# Other_Components.net
KiCad netlist of a schematic drawn in Altium Designer
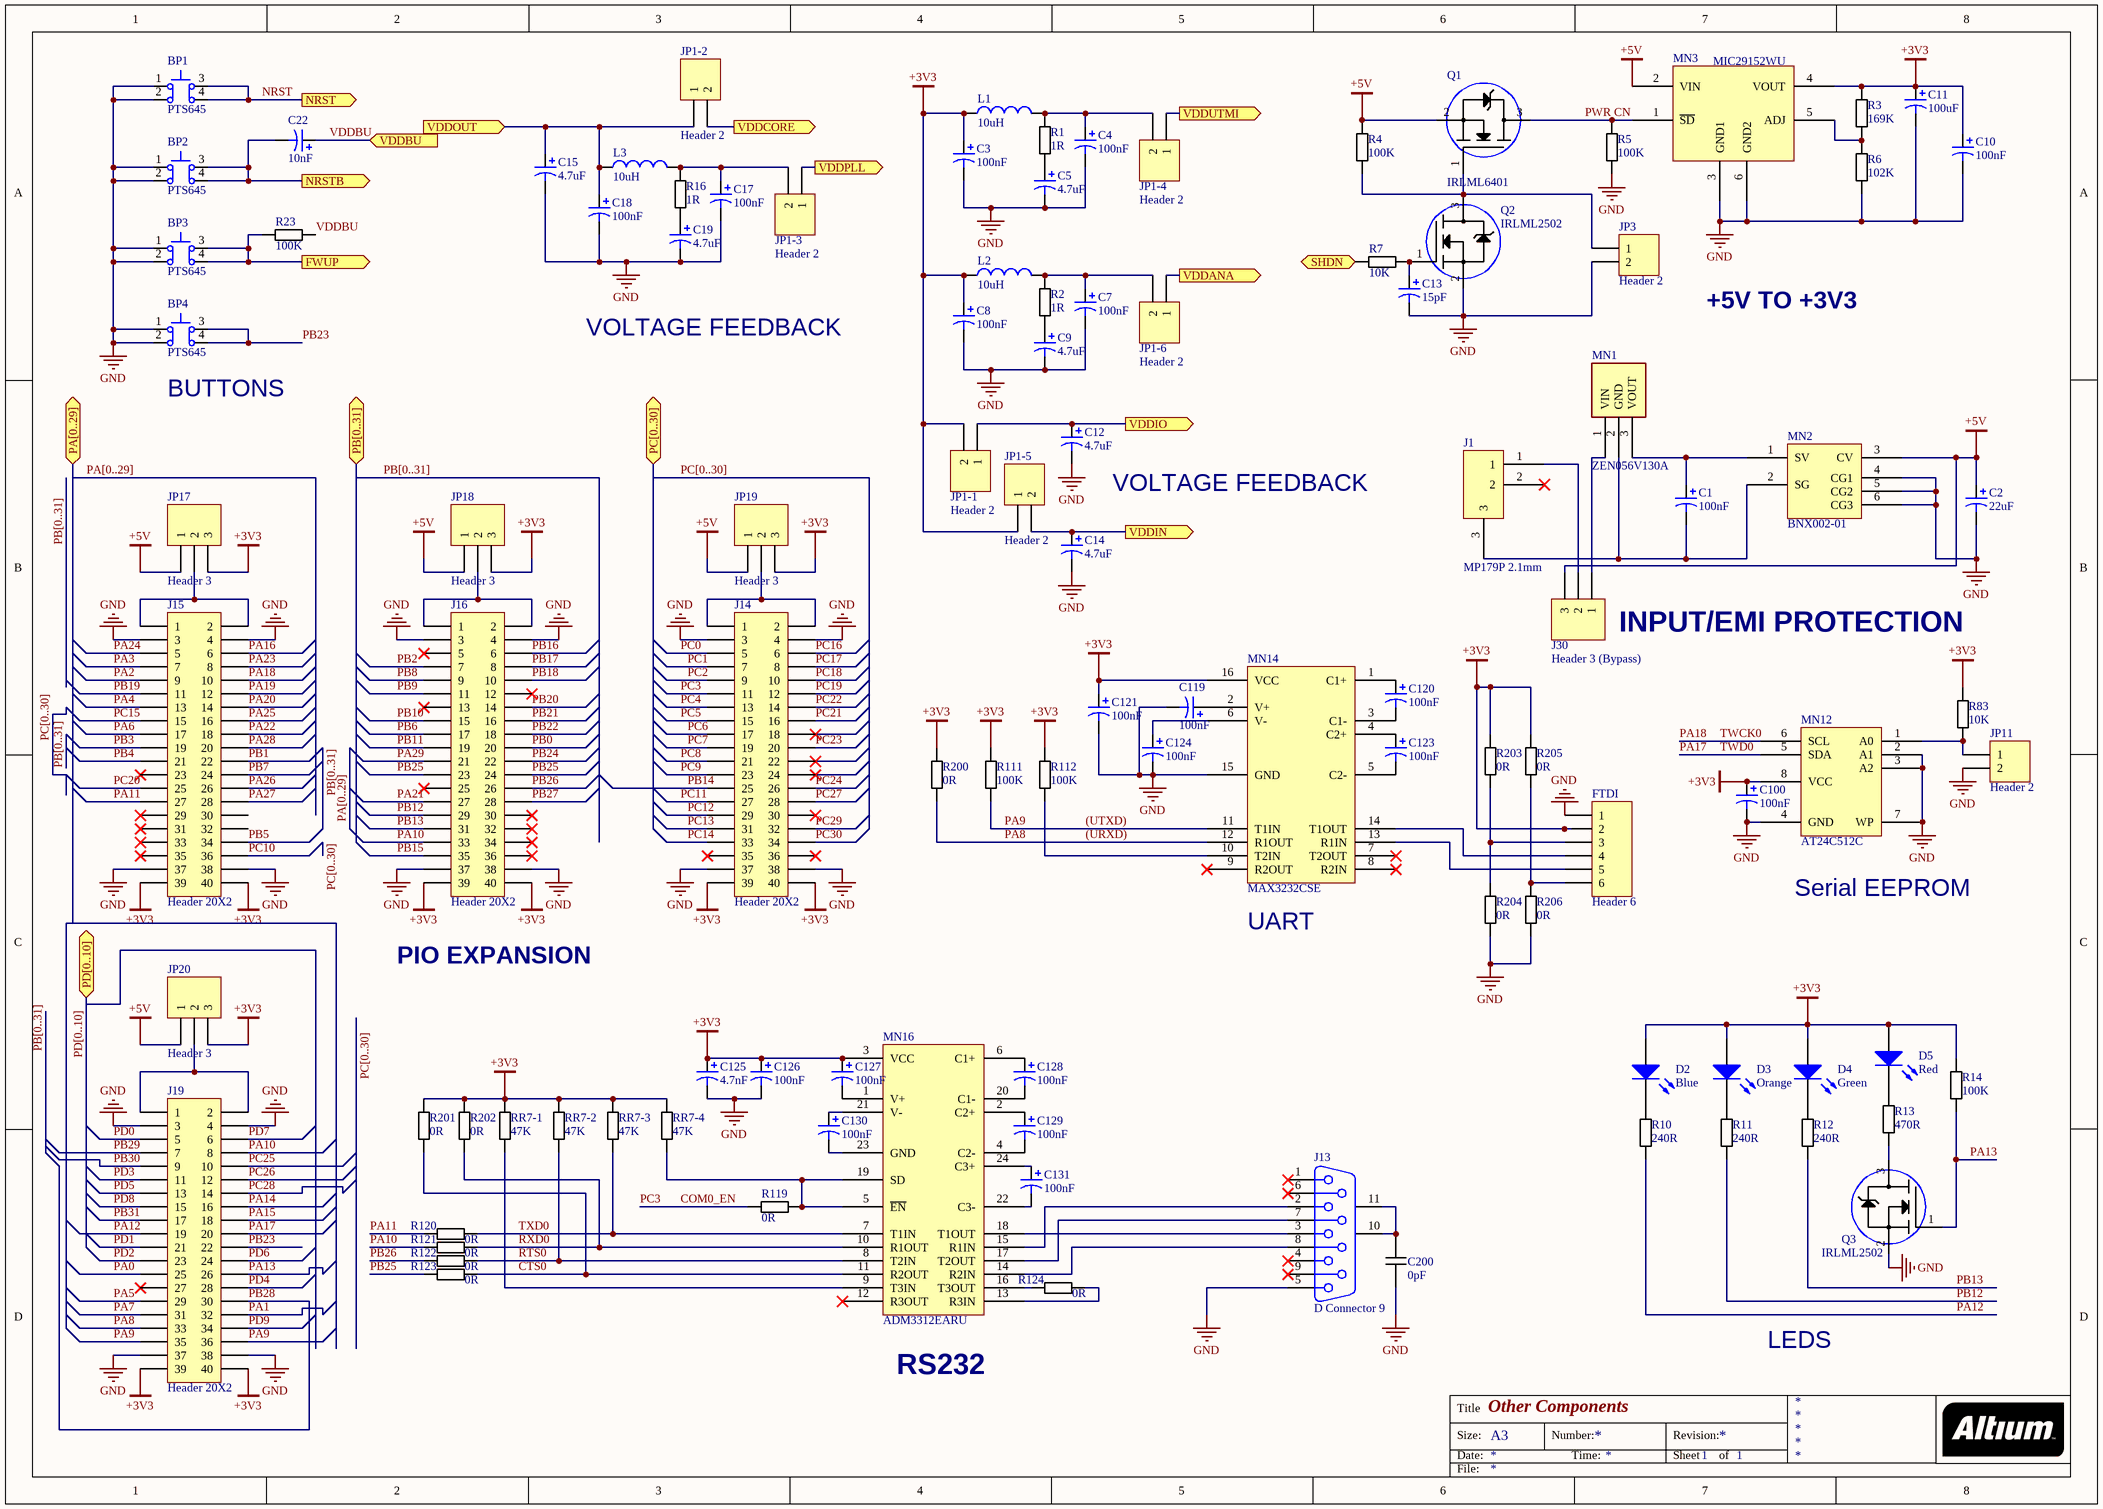
[diagram p0: Other Components.SchDoc]

(export (version "E")
  (design (tool "Eeschema 10.0.6"))
  (components
    (comp (ref "BP1")
      (value "PTS645")
      (footprint "PTS645")
      (description "Digi-Key Part Number CKN9112CT-ND")
      (fields (field (name "PUBLISHER") "Altium Limited"))
      (libsource (lib "IL Switch Push Button") (part "PTS645"))
    )
    (comp (ref "BP2")
      (value "PTS645")
      (footprint "PTS645")
      (description "Digi-Key Part Number CKN9112CT-ND")
      (fields (field (name "PUBLISHER") "Altium Limited"))
      (libsource (lib "IL Switch Push Button") (part "PTS645"))
    )
    (comp (ref "BP3")
      (value "PTS645")
      (footprint "PTS645")
      (description "Digi-Key Part Number CKN9112CT-ND")
      (fields (field (name "PUBLISHER") "Altium Limited"))
      (libsource (lib "IL Switch Push Button") (part "PTS645"))
    )
    (comp (ref "BP4")
      (value "PTS645")
      (footprint "PTS645")
      (description "Digi-Key Part Number CKN9112CT-ND")
      (fields (field (name "PUBLISHER") "Altium Limited"))
      (libsource (lib "IL Switch Push Button") (part "PTS645"))
    )
    (comp (ref "C1")
      (value "100nF")
      (footprint "0805 Cap")
      (description "Polarized Capacitor (Surface Mount)")
      (fields (field (name "Comment") "Cap Pol3") (field (name "PUBLISHER") "Altium Limited"))
      (libsource (lib "Miscellaneous Devices") (part "Cap Pol3"))
    )
    (comp (ref "C2")
      (value "22uF")
      (footprint "0805 Cap")
      (description "Not sure if this one should be 0805?")
      (fields (field (name "Comment") "Cap Pol3") (field (name "PUBLISHER") "Altium Limited"))
      (libsource (lib "Miscellaneous Devices") (part "Cap Pol3"))
    )
    (comp (ref "C3")
      (value "100nF")
      (footprint "0805 Cap")
      (description "Polarized Capacitor (Surface Mount)")
      (fields (field (name "Comment") "Cap Pol3") (field (name "PUBLISHER") "Altium Limited"))
      (libsource (lib "Miscellaneous Devices") (part "Cap Pol3"))
    )
    (comp (ref "C4")
      (value "100nF")
      (footprint "0805 Cap")
      (description "Polarized Capacitor (Surface Mount)")
      (fields (field (name "Comment") "Cap Pol3") (field (name "PUBLISHER") "Altium Limited"))
      (libsource (lib "Miscellaneous Devices") (part "Cap Pol3"))
    )
    (comp (ref "C5")
      (value "4.7uF")
      (footprint "0805 Cap")
      (description "Polarized Capacitor (Surface Mount)")
      (fields (field (name "Comment") "Cap Pol3") (field (name "PUBLISHER") "Altium Limited"))
      (libsource (lib "Miscellaneous Devices") (part "Cap Pol3"))
    )
    (comp (ref "C7")
      (value "100nF")
      (footprint "0805 Cap")
      (description "Polarized Capacitor (Surface Mount)")
      (fields (field (name "Comment") "Cap Pol3") (field (name "PUBLISHER") "Altium Limited"))
      (libsource (lib "Miscellaneous Devices") (part "Cap Pol3"))
    )
    (comp (ref "C8")
      (value "100nF")
      (footprint "0805 Cap")
      (description "Polarized Capacitor (Surface Mount)")
      (fields (field (name "Comment") "Cap Pol3") (field (name "PUBLISHER") "Altium Limited"))
      (libsource (lib "Miscellaneous Devices") (part "Cap Pol3"))
    )
    (comp (ref "C9")
      (value "4.7uF")
      (footprint "0805 Cap")
      (description "Polarized Capacitor (Surface Mount)")
      (fields (field (name "Comment") "Cap Pol3") (field (name "PUBLISHER") "Altium Limited"))
      (libsource (lib "Miscellaneous Devices") (part "Cap Pol3"))
    )
    (comp (ref "C10")
      (value "100nF")
      (footprint "0805 Cap")
      (description "Polarized Capacitor (Surface Mount)")
      (fields (field (name "Comment") "Cap Pol3") (field (name "PUBLISHER") "Altium Limited"))
      (libsource (lib "Miscellaneous Devices") (part "Cap Pol3"))
    )
    (comp (ref "C11")
      (value "100uF")
      (footprint "0805 Cap")
      (description "Polarized Capacitor (Surface Mount)")
      (fields (field (name "Comment") "Cap Pol3") (field (name "PUBLISHER") "Altium Limited"))
      (libsource (lib "Miscellaneous Devices") (part "Cap Pol3"))
    )
    (comp (ref "C12")
      (value "4.7uF")
      (footprint "0805 Cap")
      (description "Polarized Capacitor (Surface Mount)")
      (fields (field (name "Comment") "Cap Pol3") (field (name "PUBLISHER") "Altium Limited"))
      (libsource (lib "Miscellaneous Devices") (part "Cap Pol3"))
    )
    (comp (ref "C13")
      (value "15pF")
      (footprint "0805 Cap")
      (description "Polarized Capacitor (Surface Mount)")
      (fields (field (name "Comment") "Cap Pol3") (field (name "PUBLISHER") "Altium Limited"))
      (libsource (lib "Miscellaneous Devices") (part "Cap Pol3"))
    )
    (comp (ref "C14")
      (value "4.7uF")
      (footprint "0805 Cap")
      (description "Polarized Capacitor (Surface Mount)")
      (fields (field (name "Comment") "Cap Pol3") (field (name "PUBLISHER") "Altium Limited"))
      (libsource (lib "Miscellaneous Devices") (part "Cap Pol3"))
    )
    (comp (ref "C15")
      (value "4.7uF")
      (footprint "0805 Cap")
      (description "Polarized Capacitor (Surface Mount)")
      (fields (field (name "Comment") "Cap Pol3") (field (name "PUBLISHER") "Altium Limited"))
      (libsource (lib "Miscellaneous Devices") (part "Cap Pol3"))
    )
    (comp (ref "C17")
      (value "100nF")
      (footprint "0805 Cap")
      (description "Polarized Capacitor (Surface Mount)")
      (fields (field (name "Comment") "Cap Pol3") (field (name "PUBLISHER") "Altium Limited"))
      (libsource (lib "Miscellaneous Devices") (part "Cap Pol3"))
    )
    (comp (ref "C18")
      (value "100nF")
      (footprint "0805 Cap")
      (description "Polarized Capacitor (Surface Mount)")
      (fields (field (name "Comment") "Cap Pol3") (field (name "PUBLISHER") "Altium Limited"))
      (libsource (lib "Miscellaneous Devices") (part "Cap Pol3"))
    )
    (comp (ref "C19")
      (value "4.7uF")
      (footprint "0805 Cap")
      (description "Polarized Capacitor (Surface Mount)")
      (fields (field (name "Comment") "Cap Pol3") (field (name "PUBLISHER") "Altium Limited"))
      (libsource (lib "Miscellaneous Devices") (part "Cap Pol3"))
    )
    (comp (ref "C22")
      (value "10nF")
      (footprint "0805 Cap")
      (description "Polarized Capacitor (Surface Mount)")
      (fields (field (name "Comment") "Cap Pol3") (field (name "PUBLISHER") "Altium Limited"))
      (libsource (lib "Miscellaneous Devices") (part "Cap Pol3"))
    )
    (comp (ref "C100")
      (value "100nF")
      (footprint "0805 Cap")
      (description "Polarized Capacitor (Surface Mount)")
      (fields (field (name "Comment") "Cap Pol3") (field (name "PUBLISHER") "Altium Limited"))
      (libsource (lib "Miscellaneous Devices") (part "Cap Pol3"))
    )
    (comp (ref "C119")
      (value "100nF")
      (footprint "0805 Cap")
      (description "Polarized Capacitor (Surface Mount)")
      (fields (field (name "Comment") "Cap Pol3") (field (name "PUBLISHER") "Altium Limited"))
      (libsource (lib "Miscellaneous Devices") (part "Cap Pol3"))
    )
    (comp (ref "C120")
      (value "100nF")
      (footprint "0805 Cap")
      (description "Polarized Capacitor (Surface Mount)")
      (fields (field (name "Comment") "Cap Pol3") (field (name "PUBLISHER") "Altium Limited"))
      (libsource (lib "Miscellaneous Devices") (part "Cap Pol3"))
    )
    (comp (ref "C121")
      (value "100nF")
      (footprint "0805 Cap")
      (description "Polarized Capacitor (Surface Mount)")
      (fields (field (name "Comment") "Cap Pol3") (field (name "PUBLISHER") "Altium Limited"))
      (libsource (lib "Miscellaneous Devices") (part "Cap Pol3"))
    )
    (comp (ref "C123")
      (value "100nF")
      (footprint "0805 Cap")
      (description "Polarized Capacitor (Surface Mount)")
      (fields (field (name "Comment") "Cap Pol3") (field (name "PUBLISHER") "Altium Limited"))
      (libsource (lib "Miscellaneous Devices") (part "Cap Pol3"))
    )
    (comp (ref "C124")
      (value "100nF")
      (footprint "0805 Cap")
      (description "Polarized Capacitor (Surface Mount)")
      (fields (field (name "Comment") "Cap Pol3") (field (name "PUBLISHER") "Altium Limited"))
      (libsource (lib "Miscellaneous Devices") (part "Cap Pol3"))
    )
    (comp (ref "C125")
      (value "4.7nF")
      (footprint "0805 Cap")
      (description "Polarized Capacitor (Surface Mount)")
      (fields (field (name "Comment") "Cap Pol3") (field (name "PUBLISHER") "Altium Limited"))
      (libsource (lib "Miscellaneous Devices") (part "Cap Pol3"))
    )
    (comp (ref "C126")
      (value "100nF")
      (footprint "0805 Cap")
      (description "Polarized Capacitor (Surface Mount)")
      (fields (field (name "Comment") "Cap Pol3") (field (name "PUBLISHER") "Altium Limited"))
      (libsource (lib "Miscellaneous Devices") (part "Cap Pol3"))
    )
    (comp (ref "C127")
      (value "100nF")
      (footprint "0805 Cap")
      (description "Polarized Capacitor (Surface Mount)")
      (fields (field (name "Comment") "Cap Pol3") (field (name "PUBLISHER") "Altium Limited"))
      (libsource (lib "Miscellaneous Devices") (part "Cap Pol3"))
    )
    (comp (ref "C128")
      (value "100nF")
      (footprint "0805 Cap")
      (description "Polarized Capacitor (Surface Mount)")
      (fields (field (name "Comment") "Cap Pol3") (field (name "PUBLISHER") "Altium Limited"))
      (libsource (lib "Miscellaneous Devices") (part "Cap Pol3"))
    )
    (comp (ref "C129")
      (value "100nF")
      (footprint "0805 Cap")
      (description "Polarized Capacitor (Surface Mount)")
      (fields (field (name "Comment") "Cap Pol3") (field (name "PUBLISHER") "Altium Limited"))
      (libsource (lib "Miscellaneous Devices") (part "Cap Pol3"))
    )
    (comp (ref "C130")
      (value "100nF")
      (footprint "0805 Cap")
      (description "Polarized Capacitor (Surface Mount)")
      (fields (field (name "Comment") "Cap Pol3") (field (name "PUBLISHER") "Altium Limited"))
      (libsource (lib "Miscellaneous Devices") (part "Cap Pol3"))
    )
    (comp (ref "C131")
      (value "100nF")
      (footprint "0805 Cap")
      (description "Polarized Capacitor (Surface Mount)")
      (fields (field (name "Comment") "Cap Pol3") (field (name "PUBLISHER") "Altium Limited"))
      (libsource (lib "Miscellaneous Devices") (part "Cap Pol3"))
    )
    (comp (ref "C200")
      (value "0pF")
      (footprint "1206 Cap")
      (description "1206 MLCC - NP0, 5%")
      (fields (field (name "Comment") "1206 Cap"))
      (libsource (lib "Schlib1") (part "1206 MLCC - NP0, 5%"))
    )
    (comp (ref "D2")
      (value "Blue")
      (footprint "0805 LED")
      (description "Element 14 number: 2217974")
      (fields (field (name "PUBLISHER") "Altium Limited"))
      (libsource (lib "Miscellaneous Devices") (part "LED2"))
    )
    (comp (ref "D3")
      (value "Orange")
      (footprint "0805 LED")
      (description "Element 14 number: 2290332")
      (fields (field (name "PUBLISHER") "Altium Limited"))
      (libsource (lib "Miscellaneous Devices") (part "LED2"))
    )
    (comp (ref "D4")
      (value "Green")
      (footprint "0805 LED")
      (description "Element 14 number: 1686074")
      (fields (field (name "PUBLISHER") "Altium Limited"))
      (libsource (lib "Miscellaneous Devices") (part "LED2"))
    )
    (comp (ref "D5")
      (value "Red")
      (footprint "0805 LED")
      (description "Element 14 mumber: 2314402")
      (fields (field (name "PUBLISHER") "Altium Limited"))
      (libsource (lib "Miscellaneous Devices") (part "LED2"))
    )
    (comp (ref "FTDI")
      (value "Header 6")
      (footprint "HDR1X6")
      (description "Header, 6-Pin")
      (fields (field (name "PUBLISHER") "Altium Limited"))
      (libsource (lib "Miscellaneous Connectors") (part "Header 6"))
    )
    (comp (ref "J1")
      (value "MP179P 2.1mm")
      (footprint "2.1mm Jack")
      (description "Digi-Key Part Number CP-002AHPJCT-ND")
      (libsource (lib "Integrated_circuits") (part "MP179P 2.1mm"))
    )
    (comp (ref "J13")
      (value "D Connector 9")
      (footprint "DSUB1.385-2H9")
      (description "Receptacle Assembly, 9 Position, Right Angle")
      (libsource (lib "Telem") (part "D Connector 9"))
    )
    (comp (ref "J14")
      (value "Header 20X2")
      (footprint "HDR2X20")
      (description "Header, 20-Pin, Dual row")
      (fields (field (name "PUBLISHER") "Altium Limited"))
      (libsource (lib "Miscellaneous Connectors") (part "Header 20X2"))
    )
    (comp (ref "J15")
      (value "Header 20X2")
      (footprint "HDR2X20")
      (description "Header, 20-Pin, Dual row")
      (fields (field (name "PUBLISHER") "Altium Limited"))
      (libsource (lib "Miscellaneous Connectors") (part "Header 20X2"))
    )
    (comp (ref "J16")
      (value "Header 20X2")
      (footprint "HDR2X20")
      (description "Header, 20-Pin, Dual row")
      (fields (field (name "PUBLISHER") "Altium Limited"))
      (libsource (lib "Miscellaneous Connectors") (part "Header 20X2"))
    )
    (comp (ref "J19")
      (value "Header 20X2")
      (footprint "HDR2X20")
      (description "Header, 20-Pin, Dual row")
      (fields (field (name "PUBLISHER") "Altium Limited"))
      (libsource (lib "Miscellaneous Connectors") (part "Header 20X2"))
    )
    (comp (ref "J30")
      (value "Header 3 (Bypass)")
      (footprint "HDR1X3")
      (description "Header, 3-Pin")
      (fields (field (name "PUBLISHER") "Altium Limited"))
      (libsource (lib "") (part "Header 3_1"))
    )
    (comp (ref "JP1-1")
      (value "Header 2")
      (footprint "HDR1X2")
      (description "Header, 2-Pin")
      (fields (field (name "MANUFACTURER") "Molex"))
      (libsource (lib "") (part "Header 2_2"))
    )
    (comp (ref "JP1-2")
      (value "Header 2")
      (footprint "HDR1X2")
      (description "Header, 2-Pin")
      (fields (field (name "MANUFACTURER") "Molex"))
      (libsource (lib "Tray 1 Expansion Board Prototype") (part "Header 2"))
    )
    (comp (ref "JP1-3")
      (value "Header 2")
      (footprint "HDR1X2")
      (description "Header, 2-Pin")
      (fields (field (name "MANUFACTURER") "Molex"))
      (libsource (lib "") (part "Header 2_2"))
    )
    (comp (ref "JP1-4")
      (value "Header 2")
      (footprint "HDR1X2")
      (description "Header, 2-Pin")
      (fields (field (name "MANUFACTURER") "Molex"))
      (libsource (lib "") (part "Header 2_2"))
    )
    (comp (ref "JP1-5")
      (value "Header 2")
      (footprint "HDR1X2")
      (description "Header, 2-Pin")
      (fields (field (name "MANUFACTURER") "Molex"))
      (libsource (lib "Tray 1 Expansion Board Prototype") (part "Header 2"))
    )
    (comp (ref "JP1-6")
      (value "Header 2")
      (footprint "HDR1X2")
      (description "Header, 2-Pin")
      (fields (field (name "MANUFACTURER") "Molex"))
      (libsource (lib "") (part "Header 2_2"))
    )
    (comp (ref "JP3")
      (value "Header 2")
      (footprint "HDR1X2")
      (description "Header, 2-Pin")
      (fields (field (name "MANUFACTURER") "Molex"))
      (libsource (lib "") (part "Header 2_1"))
    )
    (comp (ref "JP11")
      (value "Header 2")
      (footprint "HDR1X2")
      (description "Header, 2-Pin")
      (fields (field (name "MANUFACTURER") "Molex"))
      (libsource (lib "") (part "Header 2_1"))
    )
    (comp (ref "JP17")
      (value "Header 3")
      (footprint "HDR1X3")
      (description "Header, 3-Pin")
      (fields (field (name "PUBLISHER") "Altium Limited"))
      (libsource (lib "Miscellaneous Connectors") (part "Header 3"))
    )
    (comp (ref "JP18")
      (value "Header 3")
      (footprint "HDR1X3")
      (description "Header, 3-Pin")
      (fields (field (name "PUBLISHER") "Altium Limited"))
      (libsource (lib "Miscellaneous Connectors") (part "Header 3"))
    )
    (comp (ref "JP19")
      (value "Header 3")
      (footprint "HDR1X3")
      (description "Header, 3-Pin")
      (fields (field (name "PUBLISHER") "Altium Limited"))
      (libsource (lib "Miscellaneous Connectors") (part "Header 3"))
    )
    (comp (ref "JP20")
      (value "Header 3")
      (footprint "HDR1X3")
      (description "Header, 3-Pin")
      (fields (field (name "PUBLISHER") "Altium Limited"))
      (libsource (lib "Miscellaneous Connectors") (part "Header 3"))
    )
    (comp (ref "L1")
      (value "10uH")
      (footprint "0805 Resistor")
      (description "DigiKey: 587-1691-1-ND")
      (fields (field (name "Comment") "Inductor") (field (name "PUBLISHER") "Altium Limited"))
      (libsource (lib "Miscellaneous Devices") (part "Inductor"))
    )
    (comp (ref "L2")
      (value "10uH")
      (footprint "0805 Resistor")
      (description "DigiKey: 587-1691-1-ND")
      (fields (field (name "Comment") "Inductor") (field (name "PUBLISHER") "Altium Limited"))
      (libsource (lib "Miscellaneous Devices") (part "Inductor"))
    )
    (comp (ref "L3")
      (value "10uH")
      (footprint "0805 Resistor")
      (description "DigiKey: 587-1691-1-ND")
      (fields (field (name "Comment") "Inductor") (field (name "PUBLISHER") "Altium Limited"))
      (libsource (lib "Miscellaneous Devices") (part "Inductor"))
    )
    (comp (ref "MN1")
      (value "ZEN056V130A")
      (footprint "ZEN056V130A24L")
      (description "Digi-key number: ZEN056V130A24LSCT-ND")
      (libsource (lib "Integrated_circuits") (part "ZEN0656V130A"))
    )
    (comp (ref "MN2")
      (value "BNX002-01")
      (footprint "BNX002")
      (description "Digikey number: 490-5053-ND")
      (libsource (lib "Integrated_circuits") (part "BNX002-01"))
    )
    (comp (ref "MN3")
      (value "MIC29152WU")
      (footprint "MIC29152WU")
      (description "Mircel's 1.5A LDO TO263-5. Digikey Number: 576-3367-5-ND")
      (libsource (lib "Integrated_circuits") (part "MIC29152WU"))
    )
    (comp (ref "MN12")
      (value "AT24C512C")
      (footprint "AT24C512C")
      (description "Digikey Number: AT24C512C-SSHD-TCT-ND")
      (libsource (lib "Integrated_circuits") (part "AT24C512C"))
    )
    (comp (ref "MN14")
      (value "MAX3232CSE")
      (footprint "SOIC127P570X175-16N")
      (description "Digikey Number: MAX3232CSE+-ND")
      (libsource (lib "Integrated_circuits") (part "MAX3232CSE"))
    )
    (comp (ref "MN16")
      (value "ADM3312EARU")
      (footprint "TSOP65P640X120-24N")
      (description "Digikey Number: ADM3312EARUZ-ND")
      (libsource (lib "Integrated_circuits") (part "ADM3312EARU"))
    )
    (comp (ref "Q1")
      (value "IRLML6401")
      (footprint "3 Pin SOT-23")
      (description "Digikey Part Number: IRLML6401PBFCT-ND")
      (libsource (lib "Integrated_circuits") (part "IRLML6401"))
    )
    (comp (ref "Q2")
      (value "IRLML2502")
      (footprint "3 Pin SOT-23")
      (description "DigiKey Part no: IRLML2502PBFCT-ND")
      (libsource (lib "Integrated_circuits") (part "IRLML2502"))
    )
    (comp (ref "Q3")
      (value "IRLML2502")
      (footprint "3 Pin SOT-23")
      (description "DigiKey Part no: IRLML2502PBFCT-ND")
      (libsource (lib "Integrated_circuits") (part "IRLML2502"))
    )
    (comp (ref "R1")
      (value "1R")
      (footprint "0805 Resistor")
      (description "0805 Thick Film Resistor 1%")
      (fields (field (name "Comment") "0805 Resistor"))
      (libsource (lib "Schlib1") (part "0805 Thick Film Resistor 1%"))
    )
    (comp (ref "R2")
      (value "1R")
      (footprint "0805 Resistor")
      (description "0805 Thick Film Resistor 1%")
      (fields (field (name "Comment") "0805 Resistor"))
      (libsource (lib "Schlib1") (part "0805 Thick Film Resistor 1%"))
    )
    (comp (ref "R3")
      (value "169K")
      (footprint "0805 Resistor")
      (description "0805 Thick Film Resistor 1%")
      (fields (field (name "Comment") "0805 Resistor"))
      (libsource (lib "Schlib1") (part "0805 Thick Film Resistor 1%"))
    )
    (comp (ref "R4")
      (value "100K")
      (footprint "0805 Resistor")
      (description "0805 Thick Film Resistor 1%")
      (fields (field (name "Comment") "0805 Resistor"))
      (libsource (lib "Schlib1") (part "0805 Thick Film Resistor 1%"))
    )
    (comp (ref "R5")
      (value "100K")
      (footprint "0805 Resistor")
      (description "0805 Thick Film Resistor 1%")
      (fields (field (name "Comment") "0805 Resistor"))
      (libsource (lib "Schlib1") (part "0805 Thick Film Resistor 1%"))
    )
    (comp (ref "R6")
      (value "102K")
      (footprint "0805 Resistor")
      (description "0805 Thick Film Resistor 1%")
      (fields (field (name "Comment") "0805 Resistor"))
      (libsource (lib "Schlib1") (part "0805 Thick Film Resistor 1%"))
    )
    (comp (ref "R7")
      (value "10K")
      (footprint "0805 Resistor")
      (description "0805 Thick Film Resistor 1%")
      (fields (field (name "Comment") "0805 Resistor"))
      (libsource (lib "") (part "0805 Thick Film Resistor 1%_2"))
    )
    (comp (ref "R10")
      (value "240R")
      (footprint "0805 Resistor")
      (description "0805 Thick Film Resistor 1%")
      (fields (field (name "Comment") "0805 Resistor"))
      (libsource (lib "Schlib1") (part "0805 Thick Film Resistor 1%"))
    )
    (comp (ref "R11")
      (value "240R")
      (footprint "0805 Resistor")
      (description "0805 Thick Film Resistor 1%")
      (fields (field (name "Comment") "0805 Resistor"))
      (libsource (lib "Schlib1") (part "0805 Thick Film Resistor 1%"))
    )
    (comp (ref "R12")
      (value "240R")
      (footprint "0805 Resistor")
      (description "0805 Thick Film Resistor 1%")
      (fields (field (name "Comment") "0805 Resistor"))
      (libsource (lib "Schlib1") (part "0805 Thick Film Resistor 1%"))
    )
    (comp (ref "R13")
      (value "470R")
      (footprint "0805 Resistor")
      (description "0805 Thick Film Resistor 1%")
      (fields (field (name "Comment") "0805 Resistor"))
      (libsource (lib "Schlib1") (part "0805 Thick Film Resistor 1%"))
    )
    (comp (ref "R14")
      (value "100K")
      (footprint "0805 Resistor")
      (description "0805 Thick Film Resistor 1%")
      (fields (field (name "Comment") "0805 Resistor"))
      (libsource (lib "Schlib1") (part "0805 Thick Film Resistor 1%"))
    )
    (comp (ref "R16")
      (value "1R")
      (footprint "0805 Resistor")
      (description "0805 Thick Film Resistor 1%")
      (fields (field (name "Comment") "0805 Resistor"))
      (libsource (lib "Schlib1") (part "0805 Thick Film Resistor 1%"))
    )
    (comp (ref "R23")
      (value "100K")
      (footprint "0805 Resistor")
      (description "0805 Thick Film Resistor 1%")
      (fields (field (name "Comment") "0805 Resistor"))
      (libsource (lib "") (part "0805 Thick Film Resistor 1%_1"))
    )
    (comp (ref "R83")
      (value "10K")
      (footprint "0805 Resistor")
      (description "0805 Thick Film Resistor 1%")
      (fields (field (name "Comment") "0805 Resistor"))
      (libsource (lib "Schlib1") (part "0805 Thick Film Resistor 1%"))
    )
    (comp (ref "R111")
      (value "100K")
      (footprint "0805 Resistor")
      (description "0805 Thick Film Resistor 1%")
      (fields (field (name "Comment") "0805 Resistor"))
      (libsource (lib "") (part "0805 Thick Film Resistor 1%_1_2"))
    )
    (comp (ref "R112")
      (value "100K")
      (footprint "0805 Resistor")
      (description "0805 Thick Film Resistor 1%")
      (fields (field (name "Comment") "0805 Resistor"))
      (libsource (lib "") (part "0805 Thick Film Resistor 1%_1_2"))
    )
    (comp (ref "R119")
      (value "0R")
      (footprint "0805 Resistor")
      (description "0805 Thick Film Resistor 1%")
      (fields (field (name "Comment") "0805 Resistor"))
      (libsource (lib "") (part "0805 Thick Film Resistor 1%_1"))
    )
    (comp (ref "R120")
      (value "0R")
      (footprint "0805 Resistor")
      (description "0805 Thick Film Resistor 1%")
      (fields (field (name "Comment") "0805 Resistor"))
      (libsource (lib "Schlib1") (part "0805 Thick Film Resistor 1%_1"))
    )
    (comp (ref "R121")
      (value "0R")
      (footprint "0805 Resistor")
      (description "0805 Thick Film Resistor 1%")
      (fields (field (name "Comment") "0805 Resistor"))
      (libsource (lib "Schlib1") (part "0805 Thick Film Resistor 1%_1"))
    )
    (comp (ref "R122")
      (value "0R")
      (footprint "0805 Resistor")
      (description "0805 Thick Film Resistor 1%")
      (fields (field (name "Comment") "0805 Resistor"))
      (libsource (lib "Schlib1") (part "0805 Thick Film Resistor 1%_1"))
    )
    (comp (ref "R123")
      (value "0R")
      (footprint "0805 Resistor")
      (description "0805 Thick Film Resistor 1%")
      (fields (field (name "Comment") "0805 Resistor"))
      (libsource (lib "Schlib1") (part "0805 Thick Film Resistor 1%_1"))
    )
    (comp (ref "R124")
      (value "0R")
      (footprint "0805 Resistor")
      (description "0805 Thick Film Resistor 1%")
      (fields (field (name "Comment") "0805 Resistor"))
      (libsource (lib "Schlib1") (part "0805 Thick Film Resistor 1%_1"))
    )
    (comp (ref "R200")
      (value "0R")
      (footprint "0805 Resistor")
      (description "0805 Thick Film Resistor 1%")
      (fields (field (name "Comment") "0805 Resistor"))
      (libsource (lib "Schlib1") (part "0805 Thick Film Resistor 1%"))
    )
    (comp (ref "R201")
      (value "0R")
      (footprint "0805 Resistor")
      (description "0805 Thick Film Resistor 1%")
      (fields (field (name "Comment") "0805 Resistor"))
      (libsource (lib "Schlib1") (part "0805 Thick Film Resistor 1%"))
    )
    (comp (ref "R202")
      (value "0R")
      (footprint "0805 Resistor")
      (description "0805 Thick Film Resistor 1%")
      (fields (field (name "Comment") "0805 Resistor"))
      (libsource (lib "Schlib1") (part "0805 Thick Film Resistor 1%"))
    )
    (comp (ref "R203")
      (value "0R")
      (footprint "0805 Resistor")
      (description "0805 Thick Film Resistor 1%")
      (fields (field (name "Comment") "0805 Resistor"))
      (libsource (lib "Schlib1") (part "0805 Thick Film Resistor 1%"))
    )
    (comp (ref "R204")
      (value "0R")
      (footprint "0805 Resistor")
      (description "0805 Thick Film Resistor 1%")
      (fields (field (name "Comment") "0805 Resistor"))
      (libsource (lib "Schlib1") (part "0805 Thick Film Resistor 1%"))
    )
    (comp (ref "R205")
      (value "0R")
      (footprint "0805 Resistor")
      (description "0805 Thick Film Resistor 1%")
      (fields (field (name "Comment") "0805 Resistor"))
      (libsource (lib "Schlib1") (part "0805 Thick Film Resistor 1%"))
    )
    (comp (ref "R206")
      (value "0R")
      (footprint "0805 Resistor")
      (description "0805 Thick Film Resistor 1%")
      (fields (field (name "Comment") "0805 Resistor"))
      (libsource (lib "Schlib1") (part "0805 Thick Film Resistor 1%"))
    )
    (comp (ref "RR7-1")
      (value "47K")
      (footprint "0805 Resistor")
      (description "0805 Thick Film Resistor 1%")
      (fields (field (name "Comment") "0805 Resistor"))
      (libsource (lib "") (part "0805 Thick Film Resistor 1%_1_1"))
    )
    (comp (ref "RR7-2")
      (value "47K")
      (footprint "0805 Resistor")
      (description "0805 Thick Film Resistor 1%")
      (fields (field (name "Comment") "0805 Resistor"))
      (libsource (lib "") (part "0805 Thick Film Resistor 1%_1_1"))
    )
    (comp (ref "RR7-3")
      (value "47K")
      (footprint "0805 Resistor")
      (description "0805 Thick Film Resistor 1%")
      (fields (field (name "Comment") "0805 Resistor"))
      (libsource (lib "") (part "0805 Thick Film Resistor 1%_1_1"))
    )
    (comp (ref "RR7-4")
      (value "47K")
      (footprint "0805 Resistor")
      (description "0805 Thick Film Resistor 1%")
      (fields (field (name "Comment") "0805 Resistor"))
      (libsource (lib "") (part "0805 Thick Film Resistor 1%_1_1"))
    )
  )
  (nets
    (net (code "2") (name "+3V3") (class "Default")
      (node (ref "C10") (pin "1") (pinfunction "1_1") (pintype "passive"))
      (node (ref "C100") (pin "1") (pinfunction "1_1") (pintype "passive"))
      (node (ref "C11") (pin "1") (pinfunction "1_1") (pintype "passive"))
      (node (ref "C121") (pin "1") (pinfunction "1_1") (pintype "passive"))
      (node (ref "C125") (pin "1") (pinfunction "1_1") (pintype "passive"))
      (node (ref "C126") (pin "1") (pinfunction "1_1") (pintype "passive"))
      (node (ref "C127") (pin "1") (pinfunction "1_1") (pintype "passive"))
      (node (ref "C3") (pin "1") (pinfunction "1_1") (pintype "passive"))
      (node (ref "C8") (pin "1") (pinfunction "1_1") (pintype "passive"))
      (node (ref "D2") (pin "1") (pinfunction "A_1") (pintype "passive"))
      (node (ref "D3") (pin "1") (pinfunction "A_1") (pintype "passive"))
      (node (ref "D4") (pin "1") (pinfunction "A_1") (pintype "passive"))
      (node (ref "D5") (pin "1") (pinfunction "A_1") (pintype "passive"))
      (node (ref "FTDI") (pin "2") (pinfunction "2_2") (pintype "passive"))
      (node (ref "J14") (pin "39") (pinfunction "39_39") (pintype "passive"))
      (node (ref "J14") (pin "40") (pinfunction "40_40") (pintype "passive"))
      (node (ref "J15") (pin "39") (pinfunction "39_39") (pintype "passive"))
      (node (ref "J15") (pin "40") (pinfunction "40_40") (pintype "passive"))
      (node (ref "J16") (pin "39") (pinfunction "39_39") (pintype "passive"))
      (node (ref "J16") (pin "40") (pinfunction "40_40") (pintype "passive"))
      (node (ref "J19") (pin "39") (pinfunction "39_39") (pintype "passive"))
      (node (ref "J19") (pin "40") (pinfunction "40_40") (pintype "passive"))
      (node (ref "JP1-1") (pin "2") (pinfunction "2_2") (pintype "passive"))
      (node (ref "JP1-5") (pin "1") (pinfunction "1_1") (pintype "passive"))
      (node (ref "JP17") (pin "3") (pinfunction "3_3") (pintype "passive"))
      (node (ref "JP18") (pin "3") (pinfunction "3_3") (pintype "passive"))
      (node (ref "JP19") (pin "3") (pinfunction "3_3") (pintype "passive"))
      (node (ref "JP20") (pin "3") (pinfunction "3_3") (pintype "passive"))
      (node (ref "L1") (pin "1") (pinfunction "1_1") (pintype "passive"))
      (node (ref "L2") (pin "1") (pinfunction "1_1") (pintype "passive"))
      (node (ref "MN12") (pin "8") (pinfunction "VCC_8") (pintype "passive"))
      (node (ref "MN14") (pin "16") (pinfunction "VCC_16") (pintype "passive"))
      (node (ref "MN16") (pin "3") (pinfunction "VCC_3") (pintype "passive"))
      (node (ref "MN3") (pin "4") (pinfunction "VOUT_4") (pintype "passive"))
      (node (ref "R111") (pin "2") (pinfunction "2_2") (pintype "passive"))
      (node (ref "R112") (pin "2") (pinfunction "2_2") (pintype "passive"))
      (node (ref "R14") (pin "2") (pinfunction "2_2") (pintype "passive"))
      (node (ref "R200") (pin "2") (pinfunction "2_2") (pintype "passive"))
      (node (ref "R201") (pin "2") (pinfunction "2_2") (pintype "passive"))
      (node (ref "R202") (pin "2") (pinfunction "2_2") (pintype "passive"))
      (node (ref "R203") (pin "2") (pinfunction "2_2") (pintype "passive"))
      (node (ref "R205") (pin "2") (pinfunction "2_2") (pintype "passive"))
      (node (ref "R3") (pin "2") (pinfunction "2_2") (pintype "passive"))
      (node (ref "R83") (pin "2") (pinfunction "2_2") (pintype "passive"))
      (node (ref "RR7-1") (pin "1") (pinfunction "1_1") (pintype "passive"))
      (node (ref "RR7-2") (pin "1") (pinfunction "1_1") (pintype "passive"))
      (node (ref "RR7-3") (pin "1") (pinfunction "1_1") (pintype "passive"))
      (node (ref "RR7-4") (pin "1") (pinfunction "1_1") (pintype "passive"))
    )
    (net (code "3") (name "+5V") (class "Default")
      (node (ref "C2") (pin "1") (pinfunction "1_1") (pintype "passive"))
      (node (ref "J30") (pin "3") (pinfunction "3_3") (pintype "passive"))
      (node (ref "JP17") (pin "1") (pinfunction "1_1") (pintype "passive"))
      (node (ref "JP18") (pin "1") (pinfunction "1_1") (pintype "passive"))
      (node (ref "JP19") (pin "1") (pinfunction "1_1") (pintype "passive"))
      (node (ref "JP20") (pin "1") (pinfunction "1_1") (pintype "passive"))
      (node (ref "MN2") (pin "3") (pinfunction "CV_3") (pintype "passive"))
      (node (ref "MN3") (pin "2") (pinfunction "VIN_2") (pintype "passive"))
      (node (ref "Q1") (pin "2") (pinfunction "S_2") (pintype "passive"))
      (node (ref "R4") (pin "2") (pinfunction "2_2") (pintype "passive"))
    )
    (net (code "4") (name "/CTS0") (class "Default")
      (node (ref "MN16") (pin "11") (pinfunction "R2OUT_11") (pintype "passive"))
      (node (ref "R123") (pin "2") (pinfunction "2_2") (pintype "passive"))
      (node (ref "R201") (pin "1") (pinfunction "1_1") (pintype "passive"))
    )
    (net (code "5") (name "/FWUP") (class "Default")
      (node (ref "BP3") (pin "3") (pinfunction "3_3") (pintype "passive"))
      (node (ref "BP3") (pin "4") (pinfunction "4_4") (pintype "passive"))
      (node (ref "R23") (pin "1") (pinfunction "1_1") (pintype "passive"))
    )
    (net (code "6") (name "/NRST") (class "Default")
      (node (ref "BP1") (pin "3") (pinfunction "3_3") (pintype "passive"))
      (node (ref "BP1") (pin "4") (pinfunction "4_4") (pintype "passive"))
    )
    (net (code "7") (name "/NRSTB") (class "Default")
      (node (ref "BP2") (pin "3") (pinfunction "3_3") (pintype "passive"))
      (node (ref "BP2") (pin "4") (pinfunction "4_4") (pintype "passive"))
      (node (ref "C22") (pin "2") (pinfunction "2_2") (pintype "passive"))
    )
    (net (code "8") (name "/PA0") (class "Default")
      (node (ref "J19") (pin "25") (pinfunction "25_25") (pintype "passive"))
    )
    (net (code "9") (name "/PA1") (class "Default")
      (node (ref "J19") (pin "32") (pinfunction "32_32") (pintype "passive"))
    )
    (net (code "10") (name "/PA2") (class "Default")
      (node (ref "J15") (pin "9") (pinfunction "9_9") (pintype "passive"))
    )
    (net (code "11") (name "/PA3") (class "Default")
      (node (ref "J15") (pin "7") (pinfunction "7_7") (pintype "passive"))
    )
    (net (code "12") (name "/PA4") (class "Default")
      (node (ref "J15") (pin "13") (pinfunction "13_13") (pintype "passive"))
    )
    (net (code "13") (name "/PA5") (class "Default")
      (node (ref "J19") (pin "29") (pinfunction "29_29") (pintype "passive"))
    )
    (net (code "14") (name "/PA6") (class "Default")
      (node (ref "J15") (pin "17") (pinfunction "17_17") (pintype "passive"))
    )
    (net (code "15") (name "/PA7") (class "Default")
      (node (ref "J19") (pin "31") (pinfunction "31_31") (pintype "passive"))
    )
    (net (code "16") (name "/PA8") (class "Default")
      (node (ref "J19") (pin "33") (pinfunction "33_33") (pintype "passive"))
      (node (ref "MN14") (pin "12") (pinfunction "R1OUT_12") (pintype "passive"))
      (node (ref "R200") (pin "1") (pinfunction "1_1") (pintype "passive"))
    )
    (net (code "17") (name "/PA9") (class "Default")
      (node (ref "J19") (pin "35") (pinfunction "35_35") (pintype "passive"))
      (node (ref "J19") (pin "36") (pinfunction "36_36") (pintype "passive"))
      (node (ref "MN14") (pin "11") (pinfunction "T1IN_11") (pintype "passive"))
      (node (ref "R111") (pin "1") (pinfunction "1_1") (pintype "passive"))
    )
    (net (code "18") (name "/PA10") (class "Default")
      (node (ref "J16") (pin "33") (pinfunction "33_33") (pintype "passive"))
      (node (ref "J19") (pin "8") (pinfunction "8_8") (pintype "passive"))
      (node (ref "R121") (pin "1") (pinfunction "1_1") (pintype "passive"))
    )
    (net (code "19") (name "/PA11") (class "Default")
      (node (ref "J15") (pin "27") (pinfunction "27_27") (pintype "passive"))
      (node (ref "R120") (pin "1") (pinfunction "1_1") (pintype "passive"))
    )
    (net (code "20") (name "/PA12") (class "Default")
      (node (ref "J19") (pin "19") (pinfunction "19_19") (pintype "passive"))
      (node (ref "R10") (pin "1") (pinfunction "1_1") (pintype "passive"))
    )
    (net (code "21") (name "/PA13") (class "Default")
      (node (ref "J19") (pin "26") (pinfunction "26_26") (pintype "passive"))
      (node (ref "Q3") (pin "1") (pinfunction "G_1") (pintype "passive"))
      (node (ref "R14") (pin "1") (pinfunction "1_1") (pintype "passive"))
    )
    (net (code "22") (name "/PA14") (class "Default")
      (node (ref "J19") (pin "16") (pinfunction "16_16") (pintype "passive"))
    )
    (net (code "23") (name "/PA15") (class "Default")
      (node (ref "J19") (pin "18") (pinfunction "18_18") (pintype "passive"))
    )
    (net (code "24") (name "/PA16") (class "Default")
      (node (ref "J15") (pin "6") (pinfunction "6_6") (pintype "passive"))
    )
    (net (code "25") (name "/PA17") (class "Default")
      (node (ref "J19") (pin "20") (pinfunction "20_20") (pintype "passive"))
      (node (ref "MN12") (pin "5") (pinfunction "SDA_5") (pintype "passive"))
    )
    (net (code "26") (name "/PA18") (class "Default")
      (node (ref "J15") (pin "10") (pinfunction "10_10") (pintype "passive"))
      (node (ref "MN12") (pin "6") (pinfunction "SCL_6") (pintype "passive"))
    )
    (net (code "27") (name "/PA19") (class "Default")
      (node (ref "J15") (pin "12") (pinfunction "12_12") (pintype "passive"))
    )
    (net (code "28") (name "/PA20") (class "Default")
      (node (ref "J15") (pin "14") (pinfunction "14_14") (pintype "passive"))
    )
    (net (code "29") (name "/PA21") (class "Default")
      (node (ref "J16") (pin "27") (pinfunction "27_27") (pintype "passive"))
    )
    (net (code "30") (name "/PA22") (class "Default")
      (node (ref "J15") (pin "18") (pinfunction "18_18") (pintype "passive"))
    )
    (net (code "31") (name "/PA23") (class "Default")
      (node (ref "J15") (pin "8") (pinfunction "8_8") (pintype "passive"))
    )
    (net (code "32") (name "/PA24") (class "Default")
      (node (ref "J15") (pin "5") (pinfunction "5_5") (pintype "passive"))
    )
    (net (code "33") (name "/PA25") (class "Default")
      (node (ref "J15") (pin "16") (pinfunction "16_16") (pintype "passive"))
    )
    (net (code "34") (name "/PA26") (class "Default")
      (node (ref "J15") (pin "26") (pinfunction "26_26") (pintype "passive"))
    )
    (net (code "35") (name "/PA27") (class "Default")
      (node (ref "J15") (pin "28") (pinfunction "28_28") (pintype "passive"))
    )
    (net (code "36") (name "/PA28") (class "Default")
      (node (ref "J15") (pin "20") (pinfunction "20_20") (pintype "passive"))
    )
    (net (code "37") (name "/PA29") (class "Default")
      (node (ref "J16") (pin "21") (pinfunction "21_21") (pintype "passive"))
    )
    (net (code "39") (name "/PB0") (class "Default")
      (node (ref "J16") (pin "20") (pinfunction "20_20") (pintype "passive"))
    )
    (net (code "40") (name "/PB1") (class "Default")
      (node (ref "J15") (pin "22") (pinfunction "22_22") (pintype "passive"))
    )
    (net (code "41") (name "/PB2") (class "Default")
      (node (ref "J16") (pin "7") (pinfunction "7_7") (pintype "passive"))
    )
    (net (code "42") (name "/PB3") (class "Default")
      (node (ref "J15") (pin "19") (pinfunction "19_19") (pintype "passive"))
    )
    (net (code "43") (name "/PB4") (class "Default")
      (node (ref "J15") (pin "21") (pinfunction "21_21") (pintype "passive"))
    )
    (net (code "44") (name "/PB5") (class "Default")
      (node (ref "J15") (pin "34") (pinfunction "34_34") (pintype "passive"))
    )
    (net (code "45") (name "/PB6") (class "Default")
      (node (ref "J16") (pin "17") (pinfunction "17_17") (pintype "passive"))
    )
    (net (code "46") (name "/PB7") (class "Default")
      (node (ref "J15") (pin "24") (pinfunction "24_24") (pintype "passive"))
    )
    (net (code "47") (name "/PB8") (class "Default")
      (node (ref "J16") (pin "9") (pinfunction "9_9") (pintype "passive"))
    )
    (net (code "48") (name "/PB9") (class "Default")
      (node (ref "J16") (pin "11") (pinfunction "11_11") (pintype "passive"))
    )
    (net (code "49") (name "/PB10") (class "Default")
      (node (ref "J16") (pin "15") (pinfunction "15_15") (pintype "passive"))
    )
    (net (code "50") (name "/PB11") (class "Default")
      (node (ref "J16") (pin "19") (pinfunction "19_19") (pintype "passive"))
    )
    (net (code "51") (name "/PB12") (class "Default")
      (node (ref "J16") (pin "29") (pinfunction "29_29") (pintype "passive"))
      (node (ref "R11") (pin "1") (pinfunction "1_1") (pintype "passive"))
    )
    (net (code "52") (name "/PB13") (class "Default")
      (node (ref "J16") (pin "31") (pinfunction "31_31") (pintype "passive"))
      (node (ref "R12") (pin "1") (pinfunction "1_1") (pintype "passive"))
    )
    (net (code "53") (name "/PB14") (class "Default")
      (node (ref "J14") (pin "25") (pinfunction "25_25") (pintype "passive"))
    )
    (net (code "54") (name "/PB15") (class "Default")
      (node (ref "J16") (pin "35") (pinfunction "35_35") (pintype "passive"))
    )
    (net (code "55") (name "/PB16") (class "Default")
      (node (ref "J16") (pin "6") (pinfunction "6_6") (pintype "passive"))
    )
    (net (code "56") (name "/PB17") (class "Default")
      (node (ref "J16") (pin "8") (pinfunction "8_8") (pintype "passive"))
    )
    (net (code "57") (name "/PB18") (class "Default")
      (node (ref "J16") (pin "10") (pinfunction "10_10") (pintype "passive"))
    )
    (net (code "58") (name "/PB19") (class "Default")
      (node (ref "J15") (pin "11") (pinfunction "11_11") (pintype "passive"))
    )
    (net (code "59") (name "/PB20") (class "Default")
      (node (ref "J16") (pin "14") (pinfunction "14_14") (pintype "passive"))
    )
    (net (code "60") (name "/PB21") (class "Default")
      (node (ref "J16") (pin "16") (pinfunction "16_16") (pintype "passive"))
    )
    (net (code "61") (name "/PB22") (class "Default")
      (node (ref "J16") (pin "18") (pinfunction "18_18") (pintype "passive"))
    )
    (net (code "62") (name "/PB23") (class "Default")
      (node (ref "BP4") (pin "3") (pinfunction "3_3") (pintype "passive"))
      (node (ref "BP4") (pin "4") (pinfunction "4_4") (pintype "passive"))
      (node (ref "J19") (pin "22") (pinfunction "22_22") (pintype "passive"))
    )
    (net (code "63") (name "/PB24") (class "Default")
      (node (ref "J16") (pin "22") (pinfunction "22_22") (pintype "passive"))
    )
    (net (code "64") (name "/PB25") (class "Default")
      (node (ref "J16") (pin "23") (pinfunction "23_23") (pintype "passive"))
      (node (ref "J16") (pin "24") (pinfunction "24_24") (pintype "passive"))
      (node (ref "R123") (pin "1") (pinfunction "1_1") (pintype "passive"))
    )
    (net (code "65") (name "/PB26") (class "Default")
      (node (ref "J16") (pin "26") (pinfunction "26_26") (pintype "passive"))
      (node (ref "R122") (pin "1") (pinfunction "1_1") (pintype "passive"))
    )
    (net (code "66") (name "/PB27") (class "Default")
      (node (ref "J16") (pin "28") (pinfunction "28_28") (pintype "passive"))
    )
    (net (code "67") (name "/PB28") (class "Default")
      (node (ref "J19") (pin "30") (pinfunction "30_30") (pintype "passive"))
    )
    (net (code "68") (name "/PB29") (class "Default")
      (node (ref "J19") (pin "7") (pinfunction "7_7") (pintype "passive"))
    )
    (net (code "69") (name "/PB30") (class "Default")
      (node (ref "J19") (pin "9") (pinfunction "9_9") (pintype "passive"))
    )
    (net (code "70") (name "/PB31") (class "Default")
      (node (ref "J19") (pin "17") (pinfunction "17_17") (pintype "passive"))
    )
    (net (code "72") (name "/PC0") (class "Default")
      (node (ref "J14") (pin "5") (pinfunction "5_5") (pintype "passive"))
    )
    (net (code "73") (name "/PC1") (class "Default")
      (node (ref "J14") (pin "7") (pinfunction "7_7") (pintype "passive"))
    )
    (net (code "74") (name "/PC2") (class "Default")
      (node (ref "J14") (pin "9") (pinfunction "9_9") (pintype "passive"))
    )
    (net (code "75") (name "/PC3") (class "Default")
      (node (ref "J14") (pin "11") (pinfunction "11_11") (pintype "passive"))
      (node (ref "R119") (pin "1") (pinfunction "1_1") (pintype "passive"))
    )
    (net (code "76") (name "/PC4") (class "Default")
      (node (ref "J14") (pin "13") (pinfunction "13_13") (pintype "passive"))
    )
    (net (code "77") (name "/PC5") (class "Default")
      (node (ref "J14") (pin "15") (pinfunction "15_15") (pintype "passive"))
    )
    (net (code "78") (name "/PC6") (class "Default")
      (node (ref "J14") (pin "17") (pinfunction "17_17") (pintype "passive"))
    )
    (net (code "79") (name "/PC7") (class "Default")
      (node (ref "J14") (pin "19") (pinfunction "19_19") (pintype "passive"))
    )
    (net (code "80") (name "/PC8") (class "Default")
      (node (ref "J14") (pin "21") (pinfunction "21_21") (pintype "passive"))
    )
    (net (code "81") (name "/PC9") (class "Default")
      (node (ref "J14") (pin "23") (pinfunction "23_23") (pintype "passive"))
    )
    (net (code "82") (name "/PC10") (class "Default")
      (node (ref "J15") (pin "36") (pinfunction "36_36") (pintype "passive"))
    )
    (net (code "83") (name "/PC11") (class "Default")
      (node (ref "J14") (pin "27") (pinfunction "27_27") (pintype "passive"))
    )
    (net (code "84") (name "/PC12") (class "Default")
      (node (ref "J14") (pin "29") (pinfunction "29_29") (pintype "passive"))
    )
    (net (code "85") (name "/PC13") (class "Default")
      (node (ref "J14") (pin "31") (pinfunction "31_31") (pintype "passive"))
    )
    (net (code "86") (name "/PC14") (class "Default")
      (node (ref "J14") (pin "33") (pinfunction "33_33") (pintype "passive"))
    )
    (net (code "87") (name "/PC15") (class "Default")
      (node (ref "J15") (pin "15") (pinfunction "15_15") (pintype "passive"))
    )
    (net (code "88") (name "/PC16") (class "Default")
      (node (ref "J14") (pin "6") (pinfunction "6_6") (pintype "passive"))
    )
    (net (code "89") (name "/PC17") (class "Default")
      (node (ref "J14") (pin "8") (pinfunction "8_8") (pintype "passive"))
    )
    (net (code "90") (name "/PC18") (class "Default")
      (node (ref "J14") (pin "10") (pinfunction "10_10") (pintype "passive"))
    )
    (net (code "91") (name "/PC19") (class "Default")
      (node (ref "J14") (pin "12") (pinfunction "12_12") (pintype "passive"))
    )
    (net (code "92") (name "/PC20") (class "Default")
      (node (ref "J15") (pin "25") (pinfunction "25_25") (pintype "passive"))
    )
    (net (code "93") (name "/PC21") (class "Default")
      (node (ref "J14") (pin "16") (pinfunction "16_16") (pintype "passive"))
    )
    (net (code "94") (name "/PC22") (class "Default")
      (node (ref "J14") (pin "14") (pinfunction "14_14") (pintype "passive"))
    )
    (net (code "95") (name "/PC23") (class "Default")
      (node (ref "J14") (pin "20") (pinfunction "20_20") (pintype "passive"))
    )
    (net (code "96") (name "/PC24") (class "Default")
      (node (ref "J14") (pin "26") (pinfunction "26_26") (pintype "passive"))
    )
    (net (code "97") (name "/PC25") (class "Default")
      (node (ref "J19") (pin "10") (pinfunction "10_10") (pintype "passive"))
    )
    (net (code "98") (name "/PC26") (class "Default")
      (node (ref "J19") (pin "12") (pinfunction "12_12") (pintype "passive"))
    )
    (net (code "99") (name "/PC27") (class "Default")
      (node (ref "J14") (pin "28") (pinfunction "28_28") (pintype "passive"))
    )
    (net (code "100") (name "/PC28") (class "Default")
      (node (ref "J19") (pin "14") (pinfunction "14_14") (pintype "passive"))
    )
    (net (code "101") (name "/PC29") (class "Default")
      (node (ref "J14") (pin "32") (pinfunction "32_32") (pintype "passive"))
    )
    (net (code "102") (name "/PC30") (class "Default")
      (node (ref "J14") (pin "34") (pinfunction "34_34") (pintype "passive"))
    )
    (net (code "104") (name "/PD0") (class "Default")
      (node (ref "J19") (pin "5") (pinfunction "5_5") (pintype "passive"))
    )
    (net (code "105") (name "/PD1") (class "Default")
      (node (ref "J19") (pin "21") (pinfunction "21_21") (pintype "passive"))
    )
    (net (code "106") (name "/PD2") (class "Default")
      (node (ref "J19") (pin "23") (pinfunction "23_23") (pintype "passive"))
    )
    (net (code "107") (name "/PD3") (class "Default")
      (node (ref "J19") (pin "11") (pinfunction "11_11") (pintype "passive"))
    )
    (net (code "108") (name "/PD4") (class "Default")
      (node (ref "J19") (pin "28") (pinfunction "28_28") (pintype "passive"))
    )
    (net (code "109") (name "/PD5") (class "Default")
      (node (ref "J19") (pin "13") (pinfunction "13_13") (pintype "passive"))
    )
    (net (code "110") (name "/PD6") (class "Default")
      (node (ref "J19") (pin "24") (pinfunction "24_24") (pintype "passive"))
    )
    (net (code "111") (name "/PD7") (class "Default")
      (node (ref "J19") (pin "6") (pinfunction "6_6") (pintype "passive"))
    )
    (net (code "112") (name "/PD8") (class "Default")
      (node (ref "J19") (pin "15") (pinfunction "15_15") (pintype "passive"))
    )
    (net (code "113") (name "/PD9") (class "Default")
      (node (ref "J19") (pin "34") (pinfunction "34_34") (pintype "passive"))
    )
    (net (code "115") (name "/PWR CN") (class "Default")
      (node (ref "MN3") (pin "1") (pinfunction "~{SD}_1") (pintype "passive"))
      (node (ref "Q1") (pin "3") (pinfunction "D_3") (pintype "passive"))
      (node (ref "R5") (pin "2") (pinfunction "2_2") (pintype "passive"))
    )
    (net (code "116") (name "/RTS0") (class "Default")
      (node (ref "MN16") (pin "8") (pinfunction "T2IN_8") (pintype "passive"))
      (node (ref "R122") (pin "2") (pinfunction "2_2") (pintype "passive"))
      (node (ref "RR7-2") (pin "2") (pinfunction "2_2") (pintype "passive"))
    )
    (net (code "117") (name "/RXD0") (class "Default")
      (node (ref "MN16") (pin "10") (pinfunction "R1OUT_10") (pintype "passive"))
      (node (ref "R121") (pin "2") (pinfunction "2_2") (pintype "passive"))
      (node (ref "R202") (pin "1") (pinfunction "1_1") (pintype "passive"))
    )
    (net (code "118") (name "/SHDN") (class "Default")
      (node (ref "R7") (pin "2") (pinfunction "2_2") (pintype "passive"))
    )
    (net (code "119") (name "/TXD0") (class "Default")
      (node (ref "MN16") (pin "7") (pinfunction "T1IN_7") (pintype "passive"))
      (node (ref "R120") (pin "2") (pinfunction "2_2") (pintype "passive"))
      (node (ref "RR7-3") (pin "2") (pinfunction "2_2") (pintype "passive"))
    )
    (net (code "120") (name "/VDDANA") (class "Default")
      (node (ref "JP1-6") (pin "1") (pinfunction "1_1") (pintype "passive"))
    )
    (net (code "121") (name "/VDDBU") (class "Default")
      (node (ref "C22") (pin "1") (pinfunction "1_1") (pintype "passive"))
      (node (ref "R23") (pin "2") (pinfunction "2_2") (pintype "passive"))
    )
    (net (code "122") (name "/VDDCORE") (class "Default")
      (node (ref "JP1-2") (pin "2") (pinfunction "2_2") (pintype "passive"))
    )
    (net (code "123") (name "/VDDIN") (class "Default")
      (node (ref "C14") (pin "1") (pinfunction "1_1") (pintype "passive"))
      (node (ref "JP1-5") (pin "2") (pinfunction "2_2") (pintype "passive"))
    )
    (net (code "124") (name "/VDDIO") (class "Default")
      (node (ref "C12") (pin "1") (pinfunction "1_1") (pintype "passive"))
      (node (ref "JP1-1") (pin "1") (pinfunction "1_1") (pintype "passive"))
    )
    (net (code "125") (name "/VDDOUT") (class "Default")
      (node (ref "C15") (pin "1") (pinfunction "1_1") (pintype "passive"))
      (node (ref "C18") (pin "1") (pinfunction "1_1") (pintype "passive"))
      (node (ref "JP1-2") (pin "1") (pinfunction "1_1") (pintype "passive"))
      (node (ref "L3") (pin "1") (pinfunction "1_1") (pintype "passive"))
    )
    (net (code "126") (name "/VDDPLL") (class "Default")
      (node (ref "JP1-3") (pin "1") (pinfunction "1_1") (pintype "passive"))
    )
    (net (code "127") (name "/VDDUTMI") (class "Default")
      (node (ref "JP1-4") (pin "1") (pinfunction "1_1") (pintype "passive"))
    )
    (net (code "128") (name "GND") (class "Default")
      (node (ref "BP1") (pin "1") (pinfunction "1_1") (pintype "passive"))
      (node (ref "BP1") (pin "2") (pinfunction "2_2") (pintype "passive"))
      (node (ref "BP2") (pin "1") (pinfunction "1_1") (pintype "passive"))
      (node (ref "BP2") (pin "2") (pinfunction "2_2") (pintype "passive"))
      (node (ref "BP3") (pin "1") (pinfunction "1_1") (pintype "passive"))
      (node (ref "BP3") (pin "2") (pinfunction "2_2") (pintype "passive"))
      (node (ref "BP4") (pin "1") (pinfunction "1_1") (pintype "passive"))
      (node (ref "BP4") (pin "2") (pinfunction "2_2") (pintype "passive"))
      (node (ref "C10") (pin "2") (pinfunction "2_2") (pintype "passive"))
      (node (ref "C100") (pin "2") (pinfunction "2_2") (pintype "passive"))
      (node (ref "C11") (pin "2") (pinfunction "2_2") (pintype "passive"))
      (node (ref "C119") (pin "2") (pinfunction "2_2") (pintype "passive"))
      (node (ref "C12") (pin "2") (pinfunction "2_2") (pintype "passive"))
      (node (ref "C121") (pin "2") (pinfunction "2_2") (pintype "passive"))
      (node (ref "C124") (pin "2") (pinfunction "2_2") (pintype "passive"))
      (node (ref "C125") (pin "2") (pinfunction "2_2") (pintype "passive"))
      (node (ref "C126") (pin "2") (pinfunction "2_2") (pintype "passive"))
      (node (ref "C13") (pin "2") (pinfunction "2_2") (pintype "passive"))
      (node (ref "C14") (pin "2") (pinfunction "2_2") (pintype "passive"))
      (node (ref "C15") (pin "2") (pinfunction "2_2") (pintype "passive"))
      (node (ref "C17") (pin "2") (pinfunction "2_2") (pintype "passive"))
      (node (ref "C18") (pin "2") (pinfunction "2_2") (pintype "passive"))
      (node (ref "C19") (pin "2") (pinfunction "2_2") (pintype "passive"))
      (node (ref "C2") (pin "2") (pinfunction "2_2") (pintype "passive"))
      (node (ref "C200") (pin "1") (pinfunction "1_1") (pintype "passive"))
      (node (ref "C3") (pin "2") (pinfunction "2_2") (pintype "passive"))
      (node (ref "C4") (pin "2") (pinfunction "2_2") (pintype "passive"))
      (node (ref "C5") (pin "2") (pinfunction "2_2") (pintype "passive"))
      (node (ref "C7") (pin "2") (pinfunction "2_2") (pintype "passive"))
      (node (ref "C8") (pin "2") (pinfunction "2_2") (pintype "passive"))
      (node (ref "C9") (pin "2") (pinfunction "2_2") (pintype "passive"))
      (node (ref "FTDI") (pin "1") (pinfunction "1_1") (pintype "passive"))
      (node (ref "J13") (pin "5") (pinfunction "5_5") (pintype "passive"))
      (node (ref "J14") (pin "3") (pinfunction "3_3") (pintype "passive"))
      (node (ref "J14") (pin "37") (pinfunction "37_37") (pintype "passive"))
      (node (ref "J14") (pin "38") (pinfunction "38_38") (pintype "passive"))
      (node (ref "J14") (pin "4") (pinfunction "4_4") (pintype "passive"))
      (node (ref "J15") (pin "3") (pinfunction "3_3") (pintype "passive"))
      (node (ref "J15") (pin "37") (pinfunction "37_37") (pintype "passive"))
      (node (ref "J15") (pin "38") (pinfunction "38_38") (pintype "passive"))
      (node (ref "J15") (pin "4") (pinfunction "4_4") (pintype "passive"))
      (node (ref "J16") (pin "3") (pinfunction "3_3") (pintype "passive"))
      (node (ref "J16") (pin "37") (pinfunction "37_37") (pintype "passive"))
      (node (ref "J16") (pin "38") (pinfunction "38_38") (pintype "passive"))
      (node (ref "J16") (pin "4") (pinfunction "4_4") (pintype "passive"))
      (node (ref "J19") (pin "3") (pinfunction "3_3") (pintype "passive"))
      (node (ref "J19") (pin "37") (pinfunction "37_37") (pintype "passive"))
      (node (ref "J19") (pin "38") (pinfunction "38_38") (pintype "passive"))
      (node (ref "J19") (pin "4") (pinfunction "4_4") (pintype "passive"))
      (node (ref "JP11") (pin "2") (pinfunction "2_2") (pintype "passive"))
      (node (ref "JP3") (pin "2") (pinfunction "2_2") (pintype "passive"))
      (node (ref "MN12") (pin "2") (pinfunction "A1_2") (pintype "passive"))
      (node (ref "MN12") (pin "3") (pinfunction "A2_3") (pintype "passive"))
      (node (ref "MN12") (pin "4") (pinfunction "GND_4") (pintype "passive"))
      (node (ref "MN12") (pin "7") (pinfunction "WP_7") (pintype "passive"))
      (node (ref "MN14") (pin "15") (pinfunction "GND_15") (pintype "passive"))
      (node (ref "MN2") (pin "4") (pinfunction "CG1_4") (pintype "passive"))
      (node (ref "MN2") (pin "5") (pinfunction "CG2_5") (pintype "passive"))
      (node (ref "MN2") (pin "6") (pinfunction "CG3_6") (pintype "passive"))
      (node (ref "MN3") (pin "3") (pinfunction "GND1_3") (pintype "passive"))
      (node (ref "MN3") (pin "6") (pinfunction "GND2_6") (pintype "passive"))
      (node (ref "Q2") (pin "2") (pinfunction "S_2") (pintype "passive"))
      (node (ref "Q3") (pin "2") (pinfunction "S_2") (pintype "passive"))
      (node (ref "R204") (pin "1") (pinfunction "1_1") (pintype "passive"))
      (node (ref "R206") (pin "1") (pinfunction "1_1") (pintype "passive"))
      (node (ref "R5") (pin "1") (pinfunction "1_1") (pintype "passive"))
      (node (ref "R6") (pin "1") (pinfunction "1_1") (pintype "passive"))
    )
    (net (code "129") (name "Net-(C4-Pad1)") (class "Default")
      (node (ref "C4") (pin "1") (pinfunction "1_1") (pintype "passive"))
      (node (ref "JP1-4") (pin "2") (pinfunction "2_2") (pintype "passive"))
      (node (ref "L1") (pin "2") (pinfunction "2_2") (pintype "passive"))
      (node (ref "R1") (pin "2") (pinfunction "2_2") (pintype "passive"))
    )
    (net (code "130") (name "Net-(C5-Pad1)") (class "Default")
      (node (ref "C5") (pin "1") (pinfunction "1_1") (pintype "passive"))
      (node (ref "R1") (pin "1") (pinfunction "1_1") (pintype "passive"))
    )
    (net (code "131") (name "Net-(C7-Pad1)") (class "Default")
      (node (ref "C7") (pin "1") (pinfunction "1_1") (pintype "passive"))
      (node (ref "JP1-6") (pin "2") (pinfunction "2_2") (pintype "passive"))
      (node (ref "L2") (pin "2") (pinfunction "2_2") (pintype "passive"))
      (node (ref "R2") (pin "2") (pinfunction "2_2") (pintype "passive"))
    )
    (net (code "132") (name "Net-(C9-Pad1)") (class "Default")
      (node (ref "C9") (pin "1") (pinfunction "1_1") (pintype "passive"))
      (node (ref "R2") (pin "1") (pinfunction "1_1") (pintype "passive"))
    )
    (net (code "133") (name "Net-(C17-Pad1)") (class "Default")
      (node (ref "C17") (pin "1") (pinfunction "1_1") (pintype "passive"))
      (node (ref "JP1-3") (pin "2") (pinfunction "2_2") (pintype "passive"))
      (node (ref "L3") (pin "2") (pinfunction "2_2") (pintype "passive"))
      (node (ref "R16") (pin "2") (pinfunction "2_2") (pintype "passive"))
    )
    (net (code "134") (name "Net-(C19-Pad1)") (class "Default")
      (node (ref "C19") (pin "1") (pinfunction "1_1") (pintype "passive"))
      (node (ref "R16") (pin "1") (pinfunction "1_1") (pintype "passive"))
    )
    (net (code "135") (name "Net-(D2-K)") (class "Default")
      (node (ref "D2") (pin "2") (pinfunction "K_2") (pintype "passive"))
      (node (ref "R10") (pin "2") (pinfunction "2_2") (pintype "passive"))
    )
    (net (code "136") (name "Net-(D3-K)") (class "Default")
      (node (ref "D3") (pin "2") (pinfunction "K_2") (pintype "passive"))
      (node (ref "R11") (pin "2") (pinfunction "2_2") (pintype "passive"))
    )
    (net (code "137") (name "Net-(D4-K)") (class "Default")
      (node (ref "D4") (pin "2") (pinfunction "K_2") (pintype "passive"))
      (node (ref "R12") (pin "2") (pinfunction "2_2") (pintype "passive"))
    )
    (net (code "138") (name "Net-(D5-K)") (class "Default")
      (node (ref "D5") (pin "2") (pinfunction "K_2") (pintype "passive"))
      (node (ref "R13") (pin "2") (pinfunction "2_2") (pintype "passive"))
    )
    (net (code "139") (name "Net-(FTDI-Pad3)") (class "Default")
      (node (ref "FTDI") (pin "3") (pinfunction "3_3") (pintype "passive"))
      (node (ref "R203") (pin "1") (pinfunction "1_1") (pintype "passive"))
      (node (ref "R204") (pin "2") (pinfunction "2_2") (pintype "passive"))
    )
    (net (code "140") (name "Net-(FTDI-Pad6)") (class "Default")
      (node (ref "FTDI") (pin "6") (pinfunction "6_6") (pintype "passive"))
      (node (ref "R205") (pin "1") (pinfunction "1_1") (pintype "passive"))
      (node (ref "R206") (pin "2") (pinfunction "2_2") (pintype "passive"))
    )
    (net (code "141") (name "Net-(J1-Pad1)") (class "Default")
      (node (ref "J1") (pin "1") (pinfunction "1_1") (pintype "passive"))
      (node (ref "J30") (pin "2") (pinfunction "2_2") (pintype "passive"))
    )
    (net (code "142") (name "Net-(J13-MH1)") (class "Default")
      (node (ref "C200") (pin "2") (pinfunction "2_2") (pintype "passive"))
      (node (ref "J13") (pin "10") (pinfunction "MH1_10") (pintype "passive"))
      (node (ref "J13") (pin "11") (pinfunction "MH2_11") (pintype "passive"))
    )
    (net (code "143") (name "Net-(J14-Pad1)") (class "Default")
      (node (ref "J14") (pin "1") (pinfunction "1_1") (pintype "passive"))
      (node (ref "J14") (pin "2") (pinfunction "2_2") (pintype "passive"))
      (node (ref "JP19") (pin "2") (pinfunction "2_2") (pintype "passive"))
    )
    (net (code "144") (name "Net-(J15-Pad1)") (class "Default")
      (node (ref "J15") (pin "1") (pinfunction "1_1") (pintype "passive"))
      (node (ref "J15") (pin "2") (pinfunction "2_2") (pintype "passive"))
      (node (ref "JP17") (pin "2") (pinfunction "2_2") (pintype "passive"))
    )
    (net (code "145") (name "Net-(J16-Pad1)") (class "Default")
      (node (ref "J16") (pin "1") (pinfunction "1_1") (pintype "passive"))
      (node (ref "J16") (pin "2") (pinfunction "2_2") (pintype "passive"))
      (node (ref "JP18") (pin "2") (pinfunction "2_2") (pintype "passive"))
    )
    (net (code "146") (name "Net-(J19-Pad1)") (class "Default")
      (node (ref "J19") (pin "1") (pinfunction "1_1") (pintype "passive"))
      (node (ref "J19") (pin "2") (pinfunction "2_2") (pintype "passive"))
      (node (ref "JP20") (pin "2") (pinfunction "2_2") (pintype "passive"))
    )
    (net (code "147") (name "Net-(MN1-GND)") (class "Default")
      (node (ref "C1") (pin "2") (pinfunction "2_2") (pintype "passive"))
      (node (ref "J1") (pin "3") (pinfunction "3_3") (pintype "passive"))
      (node (ref "MN1") (pin "2") (pinfunction "GND_2") (pintype "passive"))
      (node (ref "MN2") (pin "2") (pinfunction "SG_2") (pintype "passive"))
    )
    (net (code "148") (name "Net-(MN1-VIN)") (class "Default")
      (node (ref "J30") (pin "1") (pinfunction "1_1") (pintype "passive"))
      (node (ref "MN1") (pin "1") (pinfunction "VIN_1") (pintype "passive"))
    )
    (net (code "149") (name "Net-(MN1-VOUT)") (class "Default")
      (node (ref "C1") (pin "1") (pinfunction "1_1") (pintype "passive"))
      (node (ref "MN1") (pin "3") (pinfunction "VOUT_3") (pintype "passive"))
      (node (ref "MN2") (pin "1") (pinfunction "SV_1") (pintype "passive"))
    )
    (net (code "150") (name "Net-(MN3-ADJ)") (class "Default")
      (node (ref "MN3") (pin "5") (pinfunction "ADJ_5") (pintype "passive"))
      (node (ref "R3") (pin "1") (pinfunction "1_1") (pintype "passive"))
      (node (ref "R6") (pin "2") (pinfunction "2_2") (pintype "passive"))
    )
    (net (code "151") (name "Net-(MN12-A0)") (class "Default")
      (node (ref "JP11") (pin "1") (pinfunction "1_1") (pintype "passive"))
      (node (ref "MN12") (pin "1") (pinfunction "A0_1") (pintype "passive"))
      (node (ref "R83") (pin "1") (pinfunction "1_1") (pintype "passive"))
    )
    (net (code "152") (name "Net-(MN14-C1+)") (class "Default")
      (node (ref "C120") (pin "1") (pinfunction "1_1") (pintype "passive"))
      (node (ref "MN14") (pin "1") (pinfunction "C1+_1") (pintype "passive"))
    )
    (net (code "153") (name "Net-(MN14-C1-)") (class "Default")
      (node (ref "C120") (pin "2") (pinfunction "2_2") (pintype "passive"))
      (node (ref "MN14") (pin "3") (pinfunction "C1-_3") (pintype "passive"))
    )
    (net (code "154") (name "Net-(MN14-C2+)") (class "Default")
      (node (ref "C123") (pin "1") (pinfunction "1_1") (pintype "passive"))
      (node (ref "MN14") (pin "4") (pinfunction "C2+_4") (pintype "passive"))
    )
    (net (code "155") (name "Net-(MN14-C2-)") (class "Default")
      (node (ref "C123") (pin "2") (pinfunction "2_2") (pintype "passive"))
      (node (ref "MN14") (pin "5") (pinfunction "C2-_5") (pintype "passive"))
    )
    (net (code "156") (name "Net-(MN14-R1IN)") (class "Default")
      (node (ref "FTDI") (pin "5") (pinfunction "5_5") (pintype "passive"))
      (node (ref "MN14") (pin "13") (pinfunction "R1IN_13") (pintype "passive"))
    )
    (net (code "157") (name "Net-(MN14-T1OUT)") (class "Default")
      (node (ref "FTDI") (pin "4") (pinfunction "4_4") (pintype "passive"))
      (node (ref "MN14") (pin "14") (pinfunction "T1OUT_14") (pintype "passive"))
    )
    (net (code "158") (name "Net-(MN14-T2IN)") (class "Default")
      (node (ref "MN14") (pin "10") (pinfunction "T2IN_10") (pintype "passive"))
      (node (ref "R112") (pin "1") (pinfunction "1_1") (pintype "passive"))
    )
    (net (code "159") (name "Net-(MN14-V+)") (class "Default")
      (node (ref "C119") (pin "1") (pinfunction "1_1") (pintype "passive"))
      (node (ref "MN14") (pin "2") (pinfunction "V+_2") (pintype "passive"))
    )
    (net (code "160") (name "Net-(MN14-V-)") (class "Default")
      (node (ref "C124") (pin "1") (pinfunction "1_1") (pintype "passive"))
      (node (ref "MN14") (pin "6") (pinfunction "V-_6") (pintype "passive"))
    )
    (net (code "161") (name "Net-(MN16-C1+)") (class "Default")
      (node (ref "C128") (pin "1") (pinfunction "1_1") (pintype "passive"))
      (node (ref "MN16") (pin "6") (pinfunction "C1+_6") (pintype "passive"))
    )
    (net (code "162") (name "Net-(MN16-C1-)") (class "Default")
      (node (ref "C128") (pin "2") (pinfunction "2_2") (pintype "passive"))
      (node (ref "MN16") (pin "20") (pinfunction "C1-_20") (pintype "passive"))
    )
    (net (code "163") (name "Net-(MN16-C2+)") (class "Default")
      (node (ref "C129") (pin "1") (pinfunction "1_1") (pintype "passive"))
      (node (ref "MN16") (pin "2") (pinfunction "C2+_2") (pintype "passive"))
    )
    (net (code "164") (name "Net-(MN16-C2-)") (class "Default")
      (node (ref "C129") (pin "2") (pinfunction "2_2") (pintype "passive"))
      (node (ref "MN16") (pin "4") (pinfunction "C2-_4") (pintype "passive"))
    )
    (net (code "165") (name "Net-(MN16-C3+)") (class "Default")
      (node (ref "C131") (pin "1") (pinfunction "1_1") (pintype "passive"))
      (node (ref "MN16") (pin "24") (pinfunction "C3+_24") (pintype "passive"))
    )
    (net (code "166") (name "Net-(MN16-C3-)") (class "Default")
      (node (ref "C131") (pin "2") (pinfunction "2_2") (pintype "passive"))
      (node (ref "MN16") (pin "22") (pinfunction "C3-_22") (pintype "passive"))
    )
    (net (code "167") (name "Net-(MN16-GND)") (class "Default")
      (node (ref "C130") (pin "2") (pinfunction "2_2") (pintype "passive"))
      (node (ref "MN16") (pin "23") (pinfunction "GND_23") (pintype "passive"))
    )
    (net (code "168") (name "Net-(MN16-R1IN)") (class "Default")
      (node (ref "J13") (pin "2") (pinfunction "2_2") (pintype "passive"))
      (node (ref "MN16") (pin "15") (pinfunction "R1IN_15") (pintype "passive"))
    )
    (net (code "169") (name "Net-(MN16-R2IN)") (class "Default")
      (node (ref "J13") (pin "8") (pinfunction "8_8") (pintype "passive"))
      (node (ref "MN16") (pin "14") (pinfunction "R2IN_14") (pintype "passive"))
    )
    (net (code "170") (name "Net-(MN16-R3IN)") (class "Default")
      (node (ref "MN16") (pin "13") (pinfunction "R3IN_13") (pintype "passive"))
      (node (ref "R124") (pin "2") (pinfunction "2_2") (pintype "passive"))
    )
    (net (code "171") (name "Net-(MN16-SD)") (class "Default")
      (node (ref "MN16") (pin "19") (pinfunction "SD_19") (pintype "passive"))
      (node (ref "MN16") (pin "5") (pinfunction "~{EN}_5") (pintype "passive"))
      (node (ref "R119") (pin "2") (pinfunction "2_2") (pintype "passive"))
      (node (ref "RR7-4") (pin "2") (pinfunction "2_2") (pintype "passive"))
    )
    (net (code "172") (name "Net-(MN16-T1OUT)") (class "Default")
      (node (ref "J13") (pin "3") (pinfunction "3_3") (pintype "passive"))
      (node (ref "MN16") (pin "18") (pinfunction "T1OUT_18") (pintype "passive"))
    )
    (net (code "173") (name "Net-(MN16-T2OUT)") (class "Default")
      (node (ref "J13") (pin "7") (pinfunction "7_7") (pintype "passive"))
      (node (ref "MN16") (pin "17") (pinfunction "T2OUT_17") (pintype "passive"))
    )
    (net (code "174") (name "Net-(MN16-T3IN)") (class "Default")
      (node (ref "MN16") (pin "9") (pinfunction "T3IN_9") (pintype "passive"))
      (node (ref "RR7-1") (pin "2") (pinfunction "2_2") (pintype "passive"))
    )
    (net (code "175") (name "Net-(MN16-T3OUT)") (class "Default")
      (node (ref "MN16") (pin "16") (pinfunction "T3OUT_16") (pintype "passive"))
      (node (ref "R124") (pin "1") (pinfunction "1_1") (pintype "passive"))
    )
    (net (code "176") (name "Net-(MN16-V+)") (class "Default")
      (node (ref "C127") (pin "2") (pinfunction "2_2") (pintype "passive"))
      (node (ref "MN16") (pin "1") (pinfunction "V+_1") (pintype "passive"))
    )
    (net (code "177") (name "Net-(MN16-V-)") (class "Default")
      (node (ref "C130") (pin "1") (pinfunction "1_1") (pintype "passive"))
      (node (ref "MN16") (pin "21") (pinfunction "V-_21") (pintype "passive"))
    )
    (net (code "178") (name "Net-(Q1-G)") (class "Default")
      (node (ref "JP3") (pin "1") (pinfunction "1_1") (pintype "passive"))
      (node (ref "Q1") (pin "1") (pinfunction "G_1") (pintype "passive"))
      (node (ref "Q2") (pin "3") (pinfunction "D_3") (pintype "passive"))
      (node (ref "R4") (pin "1") (pinfunction "1_1") (pintype "passive"))
    )
    (net (code "179") (name "Net-(Q2-G)") (class "Default")
      (node (ref "C13") (pin "1") (pinfunction "1_1") (pintype "passive"))
      (node (ref "Q2") (pin "1") (pinfunction "G_1") (pintype "passive"))
      (node (ref "R7") (pin "1") (pinfunction "1_1") (pintype "passive"))
    )
    (net (code "180") (name "Net-(Q3-D)") (class "Default")
      (node (ref "Q3") (pin "3") (pinfunction "D_3") (pintype "passive"))
      (node (ref "R13") (pin "1") (pinfunction "1_1") (pintype "passive"))
    )
    (net (code "181") (name "unconnected-(J1-Pad2)") (class "Default")
      (node (ref "J1") (pin "2") (pinfunction "2_2") (pintype "passive+no_connect"))
    )
    (net (code "182") (name "unconnected-(J13-Pad1)") (class "Default")
      (node (ref "J13") (pin "1") (pinfunction "1_1") (pintype "passive+no_connect"))
    )
    (net (code "183") (name "unconnected-(J13-Pad4)") (class "Default")
      (node (ref "J13") (pin "4") (pinfunction "4_4") (pintype "passive+no_connect"))
    )
    (net (code "184") (name "unconnected-(J13-Pad6)") (class "Default")
      (node (ref "J13") (pin "6") (pinfunction "6_6") (pintype "passive+no_connect"))
    )
    (net (code "185") (name "unconnected-(J13-Pad9)") (class "Default")
      (node (ref "J13") (pin "9") (pinfunction "9_9") (pintype "passive+no_connect"))
    )
    (net (code "186") (name "unconnected-(J14-Pad18)") (class "Default")
      (node (ref "J14") (pin "18") (pinfunction "18_18") (pintype "passive+no_connect"))
    )
    (net (code "187") (name "unconnected-(J14-Pad22)") (class "Default")
      (node (ref "J14") (pin "22") (pinfunction "22_22") (pintype "passive+no_connect"))
    )
    (net (code "188") (name "unconnected-(J14-Pad24)") (class "Default")
      (node (ref "J14") (pin "24") (pinfunction "24_24") (pintype "passive+no_connect"))
    )
    (net (code "189") (name "unconnected-(J14-Pad30)") (class "Default")
      (node (ref "J14") (pin "30") (pinfunction "30_30") (pintype "passive+no_connect"))
    )
    (net (code "190") (name "unconnected-(J14-Pad35)") (class "Default")
      (node (ref "J14") (pin "35") (pinfunction "35_35") (pintype "passive+no_connect"))
    )
    (net (code "191") (name "unconnected-(J14-Pad36)") (class "Default")
      (node (ref "J14") (pin "36") (pinfunction "36_36") (pintype "passive+no_connect"))
    )
    (net (code "192") (name "unconnected-(J15-Pad23)") (class "Default")
      (node (ref "J15") (pin "23") (pinfunction "23_23") (pintype "passive+no_connect"))
    )
    (net (code "193") (name "unconnected-(J15-Pad29)") (class "Default")
      (node (ref "J15") (pin "29") (pinfunction "29_29") (pintype "passive+no_connect"))
    )
    (net (code "194") (name "unconnected-(J15-Pad30)") (class "Default")
      (node (ref "J15") (pin "30") (pinfunction "30_30") (pintype "passive"))
    )
    (net (code "195") (name "unconnected-(J15-Pad31)") (class "Default")
      (node (ref "J15") (pin "31") (pinfunction "31_31") (pintype "passive+no_connect"))
    )
    (net (code "196") (name "unconnected-(J15-Pad32)") (class "Default")
      (node (ref "J15") (pin "32") (pinfunction "32_32") (pintype "passive"))
    )
    (net (code "197") (name "unconnected-(J15-Pad33)") (class "Default")
      (node (ref "J15") (pin "33") (pinfunction "33_33") (pintype "passive+no_connect"))
    )
    (net (code "198") (name "unconnected-(J15-Pad35)") (class "Default")
      (node (ref "J15") (pin "35") (pinfunction "35_35") (pintype "passive+no_connect"))
    )
    (net (code "199") (name "unconnected-(J16-Pad5)") (class "Default")
      (node (ref "J16") (pin "5") (pinfunction "5_5") (pintype "passive+no_connect"))
    )
    (net (code "200") (name "unconnected-(J16-Pad12)") (class "Default")
      (node (ref "J16") (pin "12") (pinfunction "12_12") (pintype "passive+no_connect"))
    )
    (net (code "201") (name "unconnected-(J16-Pad13)") (class "Default")
      (node (ref "J16") (pin "13") (pinfunction "13_13") (pintype "passive+no_connect"))
    )
    (net (code "202") (name "unconnected-(J16-Pad25)") (class "Default")
      (node (ref "J16") (pin "25") (pinfunction "25_25") (pintype "passive+no_connect"))
    )
    (net (code "203") (name "unconnected-(J16-Pad30)") (class "Default")
      (node (ref "J16") (pin "30") (pinfunction "30_30") (pintype "passive+no_connect"))
    )
    (net (code "204") (name "unconnected-(J16-Pad32)") (class "Default")
      (node (ref "J16") (pin "32") (pinfunction "32_32") (pintype "passive+no_connect"))
    )
    (net (code "205") (name "unconnected-(J16-Pad34)") (class "Default")
      (node (ref "J16") (pin "34") (pinfunction "34_34") (pintype "passive+no_connect"))
    )
    (net (code "206") (name "unconnected-(J16-Pad36)") (class "Default")
      (node (ref "J16") (pin "36") (pinfunction "36_36") (pintype "passive+no_connect"))
    )
    (net (code "207") (name "unconnected-(J19-Pad27)") (class "Default")
      (node (ref "J19") (pin "27") (pinfunction "27_27") (pintype "passive+no_connect"))
    )
    (net (code "208") (name "unconnected-(MN14-R2IN-Pad8)") (class "Default")
      (node (ref "MN14") (pin "8") (pinfunction "R2IN_8") (pintype "passive+no_connect"))
    )
    (net (code "209") (name "unconnected-(MN14-R2OUT-Pad9)") (class "Default")
      (node (ref "MN14") (pin "9") (pinfunction "R2OUT_9") (pintype "passive+no_connect"))
    )
    (net (code "210") (name "unconnected-(MN14-T2OUT-Pad7)") (class "Default")
      (node (ref "MN14") (pin "7") (pinfunction "T2OUT_7") (pintype "passive+no_connect"))
    )
    (net (code "211") (name "unconnected-(MN16-R3OUT-Pad12)") (class "Default")
      (node (ref "MN16") (pin "12") (pinfunction "R3OUT_12") (pintype "passive+no_connect"))
    )
  )
)
